# Multiplexers.net
KiCad netlist of a schematic drawn in Altium Designer
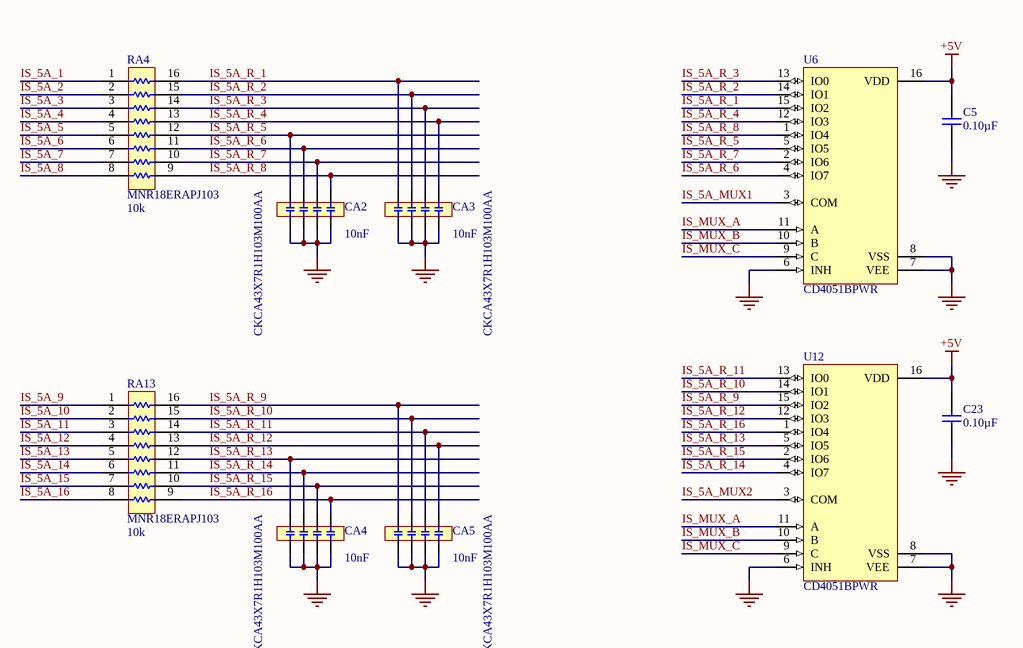
[diagram p0: Multiplexers.SchDoc]

(export (version "E")
  (design (tool "Eeschema 10.0.6"))
  (components
    (comp (ref "C5")
      (value "0.10µF")
      (footprint "CAP-0402-M")
      (fields
        (field (name "PART NUMBER") "CC0402KRX7R7BB104")
        (field (name "TOLERANCE") "±10%")
        (field (name "VOLTAGE") "16V")
      )
      (libsource (lib "Capacitors") (part "Capacitor"))
    )
    (comp (ref "C23")
      (value "0.10µF")
      (footprint "CAP-0402-M")
      (fields
        (field (name "PART NUMBER") "CC0402KRX7R7BB104")
        (field (name "TOLERANCE") "±10%")
        (field (name "VOLTAGE") "16V")
      )
      (libsource (lib "Capacitors") (part "Capacitor"))
    )
    (comp (ref "CA2")
      (value "CKCA43X7R1H103M100AA")
      (footprint "CAF-80P319X159-8N")
      (fields (field (name "ALTIUM_VALUE") "10nF"))
      (libsource (lib "PDU-UV17") (part "CKCA43X7R1H103M100AA"))
    )
    (comp (ref "CA3")
      (value "CKCA43X7R1H103M100AA")
      (footprint "CAF-80P319X159-8N")
      (fields (field (name "ALTIUM_VALUE") "10nF"))
      (libsource (lib "PDU-UV17") (part "CKCA43X7R1H103M100AA"))
    )
    (comp (ref "CA4")
      (value "CKCA43X7R1H103M100AA")
      (footprint "CAF-80P319X159-8N")
      (fields (field (name "ALTIUM_VALUE") "10nF"))
      (libsource (lib "PDU-UV17") (part "CKCA43X7R1H103M100AA"))
    )
    (comp (ref "CA5")
      (value "CKCA43X7R1H103M100AA")
      (footprint "CAF-80P319X159-8N")
      (fields (field (name "ALTIUM_VALUE") "10nF"))
      (libsource (lib "") (part "CKCA43X7R1H103M100AA_1"))
    )
    (comp (ref "RA4")
      (value "MNR18ERAPJ103")
      (footprint "CAC-50P379X150-16N")
      (fields (field (name "ALTIUM_VALUE") "10k"))
      (libsource (lib "PDU-UV17") (part "MNR18ERAPJ103"))
    )
    (comp (ref "RA13")
      (value "MNR18ERAPJ103")
      (footprint "CAC-50P379X150-16N")
      (fields (field (name "ALTIUM_VALUE") "10k"))
      (libsource (lib "PDU-UV17") (part "MNR18ERAPJ103"))
    )
    (comp (ref "U6")
      (value "CD4051BPWR")
      (footprint "TSOP65P640X120-16N")
      (libsource (lib "PDU-UV17") (part "CD4051BPWR"))
    )
    (comp (ref "U12")
      (value "CD4051BPWR")
      (footprint "TSOP65P640X120-16N")
      (libsource (lib "PDU-UV17") (part "CD4051BPWR"))
    )
  )
  (nets
    (net (code "1") (name "+5V") (class "Default")
      (node (ref "C23") (pin "2") (pinfunction "2_2") (pintype "passive"))
      (node (ref "C5") (pin "2") (pinfunction "2_2") (pintype "passive"))
      (node (ref "U12") (pin "16") (pinfunction "VDD_16") (pintype "power_in"))
      (node (ref "U6") (pin "16") (pinfunction "VDD_16") (pintype "power_in"))
    )
    (net (code "2") (name "/IS_5A_1") (class "Default")
      (node (ref "RA4") (pin "1") (pinfunction "1_1") (pintype "passive"))
    )
    (net (code "3") (name "/IS_5A_2") (class "Default")
      (node (ref "RA4") (pin "2") (pinfunction "2_2") (pintype "passive"))
    )
    (net (code "4") (name "/IS_5A_3") (class "Default")
      (node (ref "RA4") (pin "3") (pinfunction "3_3") (pintype "passive"))
    )
    (net (code "5") (name "/IS_5A_4") (class "Default")
      (node (ref "RA4") (pin "4") (pinfunction "4_4") (pintype "passive"))
    )
    (net (code "6") (name "/IS_5A_5") (class "Default")
      (node (ref "RA4") (pin "5") (pinfunction "5_5") (pintype "passive"))
    )
    (net (code "7") (name "/IS_5A_6") (class "Default")
      (node (ref "RA4") (pin "6") (pinfunction "6_6") (pintype "passive"))
    )
    (net (code "8") (name "/IS_5A_7") (class "Default")
      (node (ref "RA4") (pin "7") (pinfunction "7_7") (pintype "passive"))
    )
    (net (code "9") (name "/IS_5A_8") (class "Default")
      (node (ref "RA4") (pin "8") (pinfunction "8_8") (pintype "passive"))
    )
    (net (code "10") (name "/IS_5A_9") (class "Default")
      (node (ref "RA13") (pin "1") (pinfunction "1_1") (pintype "passive"))
    )
    (net (code "11") (name "/IS_5A_10") (class "Default")
      (node (ref "RA13") (pin "2") (pinfunction "2_2") (pintype "passive"))
    )
    (net (code "12") (name "/IS_5A_11") (class "Default")
      (node (ref "RA13") (pin "3") (pinfunction "3_3") (pintype "passive"))
    )
    (net (code "13") (name "/IS_5A_12") (class "Default")
      (node (ref "RA13") (pin "4") (pinfunction "4_4") (pintype "passive"))
    )
    (net (code "14") (name "/IS_5A_13") (class "Default")
      (node (ref "RA13") (pin "5") (pinfunction "5_5") (pintype "passive"))
    )
    (net (code "15") (name "/IS_5A_14") (class "Default")
      (node (ref "RA13") (pin "6") (pinfunction "6_6") (pintype "passive"))
    )
    (net (code "16") (name "/IS_5A_15") (class "Default")
      (node (ref "RA13") (pin "7") (pinfunction "7_7") (pintype "passive"))
    )
    (net (code "17") (name "/IS_5A_16") (class "Default")
      (node (ref "RA13") (pin "8") (pinfunction "8_8") (pintype "passive"))
    )
    (net (code "18") (name "/IS_5A_MUX1") (class "Default")
      (node (ref "U6") (pin "3") (pinfunction "COM_3") (pintype "bidirectional"))
    )
    (net (code "19") (name "/IS_5A_MUX2") (class "Default")
      (node (ref "U12") (pin "3") (pinfunction "COM_3") (pintype "bidirectional"))
    )
    (net (code "20") (name "/IS_5A_R_1") (class "Default")
      (node (ref "CA3") (pin "5") (pinfunction "5_5") (pintype "passive"))
      (node (ref "RA4") (pin "16") (pinfunction "16_16") (pintype "passive"))
      (node (ref "U6") (pin "15") (pinfunction "IO2_15") (pintype "bidirectional"))
    )
    (net (code "21") (name "/IS_5A_R_2") (class "Default")
      (node (ref "CA3") (pin "6") (pinfunction "6_6") (pintype "passive"))
      (node (ref "RA4") (pin "15") (pinfunction "15_15") (pintype "passive"))
      (node (ref "U6") (pin "14") (pinfunction "IO1_14") (pintype "bidirectional"))
    )
    (net (code "22") (name "/IS_5A_R_3") (class "Default")
      (node (ref "CA3") (pin "7") (pinfunction "7_7") (pintype "passive"))
      (node (ref "RA4") (pin "14") (pinfunction "14_14") (pintype "passive"))
      (node (ref "U6") (pin "13") (pinfunction "IO0_13") (pintype "bidirectional"))
    )
    (net (code "23") (name "/IS_5A_R_4") (class "Default")
      (node (ref "CA3") (pin "8") (pinfunction "8_8") (pintype "passive"))
      (node (ref "RA4") (pin "13") (pinfunction "13_13") (pintype "passive"))
      (node (ref "U6") (pin "12") (pinfunction "IO3_12") (pintype "bidirectional"))
    )
    (net (code "24") (name "/IS_5A_R_5") (class "Default")
      (node (ref "CA2") (pin "5") (pinfunction "5_5") (pintype "passive"))
      (node (ref "RA4") (pin "12") (pinfunction "12_12") (pintype "passive"))
      (node (ref "U6") (pin "5") (pinfunction "IO5_5") (pintype "bidirectional"))
    )
    (net (code "25") (name "/IS_5A_R_6") (class "Default")
      (node (ref "CA2") (pin "6") (pinfunction "6_6") (pintype "passive"))
      (node (ref "RA4") (pin "11") (pinfunction "11_11") (pintype "passive"))
      (node (ref "U6") (pin "4") (pinfunction "IO7_4") (pintype "bidirectional"))
    )
    (net (code "26") (name "/IS_5A_R_7") (class "Default")
      (node (ref "CA2") (pin "7") (pinfunction "7_7") (pintype "passive"))
      (node (ref "RA4") (pin "10") (pinfunction "10_10") (pintype "passive"))
      (node (ref "U6") (pin "2") (pinfunction "IO6_2") (pintype "bidirectional"))
    )
    (net (code "27") (name "/IS_5A_R_8") (class "Default")
      (node (ref "CA2") (pin "8") (pinfunction "8_8") (pintype "passive"))
      (node (ref "RA4") (pin "9") (pinfunction "9_9") (pintype "passive"))
      (node (ref "U6") (pin "1") (pinfunction "IO4_1") (pintype "bidirectional"))
    )
    (net (code "28") (name "/IS_5A_R_9") (class "Default")
      (node (ref "CA5") (pin "1") (pinfunction "1_1") (pintype "passive"))
      (node (ref "RA13") (pin "16") (pinfunction "16_16") (pintype "passive"))
      (node (ref "U12") (pin "15") (pinfunction "IO2_15") (pintype "bidirectional"))
    )
    (net (code "29") (name "/IS_5A_R_10") (class "Default")
      (node (ref "CA5") (pin "2") (pinfunction "2_2") (pintype "passive"))
      (node (ref "RA13") (pin "15") (pinfunction "15_15") (pintype "passive"))
      (node (ref "U12") (pin "14") (pinfunction "IO1_14") (pintype "bidirectional"))
    )
    (net (code "30") (name "/IS_5A_R_11") (class "Default")
      (node (ref "CA5") (pin "3") (pinfunction "3_3") (pintype "passive"))
      (node (ref "RA13") (pin "14") (pinfunction "14_14") (pintype "passive"))
      (node (ref "U12") (pin "13") (pinfunction "IO0_13") (pintype "bidirectional"))
    )
    (net (code "31") (name "/IS_5A_R_12") (class "Default")
      (node (ref "CA5") (pin "4") (pinfunction "4_4") (pintype "passive"))
      (node (ref "RA13") (pin "13") (pinfunction "13_13") (pintype "passive"))
      (node (ref "U12") (pin "12") (pinfunction "IO3_12") (pintype "bidirectional"))
    )
    (net (code "32") (name "/IS_5A_R_13") (class "Default")
      (node (ref "CA4") (pin "5") (pinfunction "5_5") (pintype "passive"))
      (node (ref "RA13") (pin "12") (pinfunction "12_12") (pintype "passive"))
      (node (ref "U12") (pin "5") (pinfunction "IO5_5") (pintype "bidirectional"))
    )
    (net (code "33") (name "/IS_5A_R_14") (class "Default")
      (node (ref "CA4") (pin "6") (pinfunction "6_6") (pintype "passive"))
      (node (ref "RA13") (pin "11") (pinfunction "11_11") (pintype "passive"))
      (node (ref "U12") (pin "4") (pinfunction "IO7_4") (pintype "bidirectional"))
    )
    (net (code "34") (name "/IS_5A_R_15") (class "Default")
      (node (ref "CA4") (pin "7") (pinfunction "7_7") (pintype "passive"))
      (node (ref "RA13") (pin "10") (pinfunction "10_10") (pintype "passive"))
      (node (ref "U12") (pin "2") (pinfunction "IO6_2") (pintype "bidirectional"))
    )
    (net (code "35") (name "/IS_5A_R_16") (class "Default")
      (node (ref "CA4") (pin "8") (pinfunction "8_8") (pintype "passive"))
      (node (ref "RA13") (pin "9") (pinfunction "9_9") (pintype "passive"))
      (node (ref "U12") (pin "1") (pinfunction "IO4_1") (pintype "bidirectional"))
    )
    (net (code "36") (name "/IS_MUX_A") (class "Default")
      (node (ref "U12") (pin "11") (pinfunction "A_11") (pintype "input"))
      (node (ref "U6") (pin "11") (pinfunction "A_11") (pintype "input"))
    )
    (net (code "37") (name "/IS_MUX_B") (class "Default")
      (node (ref "U12") (pin "10") (pinfunction "B_10") (pintype "input"))
      (node (ref "U6") (pin "10") (pinfunction "B_10") (pintype "input"))
    )
    (net (code "38") (name "/IS_MUX_C") (class "Default")
      (node (ref "U12") (pin "9") (pinfunction "C_9") (pintype "input"))
      (node (ref "U6") (pin "9") (pinfunction "C_9") (pintype "input"))
    )
    (net (code "39") (name "GND") (class "Default")
      (node (ref "C23") (pin "1") (pinfunction "1_1") (pintype "passive"))
      (node (ref "C5") (pin "1") (pinfunction "1_1") (pintype "passive"))
      (node (ref "CA2") (pin "1") (pinfunction "1_1") (pintype "passive"))
      (node (ref "CA2") (pin "2") (pinfunction "2_2") (pintype "passive"))
      (node (ref "CA2") (pin "3") (pinfunction "3_3") (pintype "passive"))
      (node (ref "CA2") (pin "4") (pinfunction "4_4") (pintype "passive"))
      (node (ref "CA3") (pin "1") (pinfunction "1_1") (pintype "passive"))
      (node (ref "CA3") (pin "2") (pinfunction "2_2") (pintype "passive"))
      (node (ref "CA3") (pin "3") (pinfunction "3_3") (pintype "passive"))
      (node (ref "CA3") (pin "4") (pinfunction "4_4") (pintype "passive"))
      (node (ref "CA4") (pin "1") (pinfunction "1_1") (pintype "passive"))
      (node (ref "CA4") (pin "2") (pinfunction "2_2") (pintype "passive"))
      (node (ref "CA4") (pin "3") (pinfunction "3_3") (pintype "passive"))
      (node (ref "CA4") (pin "4") (pinfunction "4_4") (pintype "passive"))
      (node (ref "CA5") (pin "5") (pinfunction "5_5") (pintype "passive"))
      (node (ref "CA5") (pin "6") (pinfunction "6_6") (pintype "passive"))
      (node (ref "CA5") (pin "7") (pinfunction "7_7") (pintype "passive"))
      (node (ref "CA5") (pin "8") (pinfunction "8_8") (pintype "passive"))
      (node (ref "U12") (pin "6") (pinfunction "INH_6") (pintype "input"))
      (node (ref "U12") (pin "7") (pinfunction "VEE_7") (pintype "power_in"))
      (node (ref "U12") (pin "8") (pinfunction "VSS_8") (pintype "power_in"))
      (node (ref "U6") (pin "6") (pinfunction "INH_6") (pintype "input"))
      (node (ref "U6") (pin "7") (pinfunction "VEE_7") (pintype "power_in"))
      (node (ref "U6") (pin "8") (pinfunction "VSS_8") (pintype "power_in"))
    )
  )
)
